# CH340-Sch.net
KiCad netlist of a schematic drawn in Altium Designer
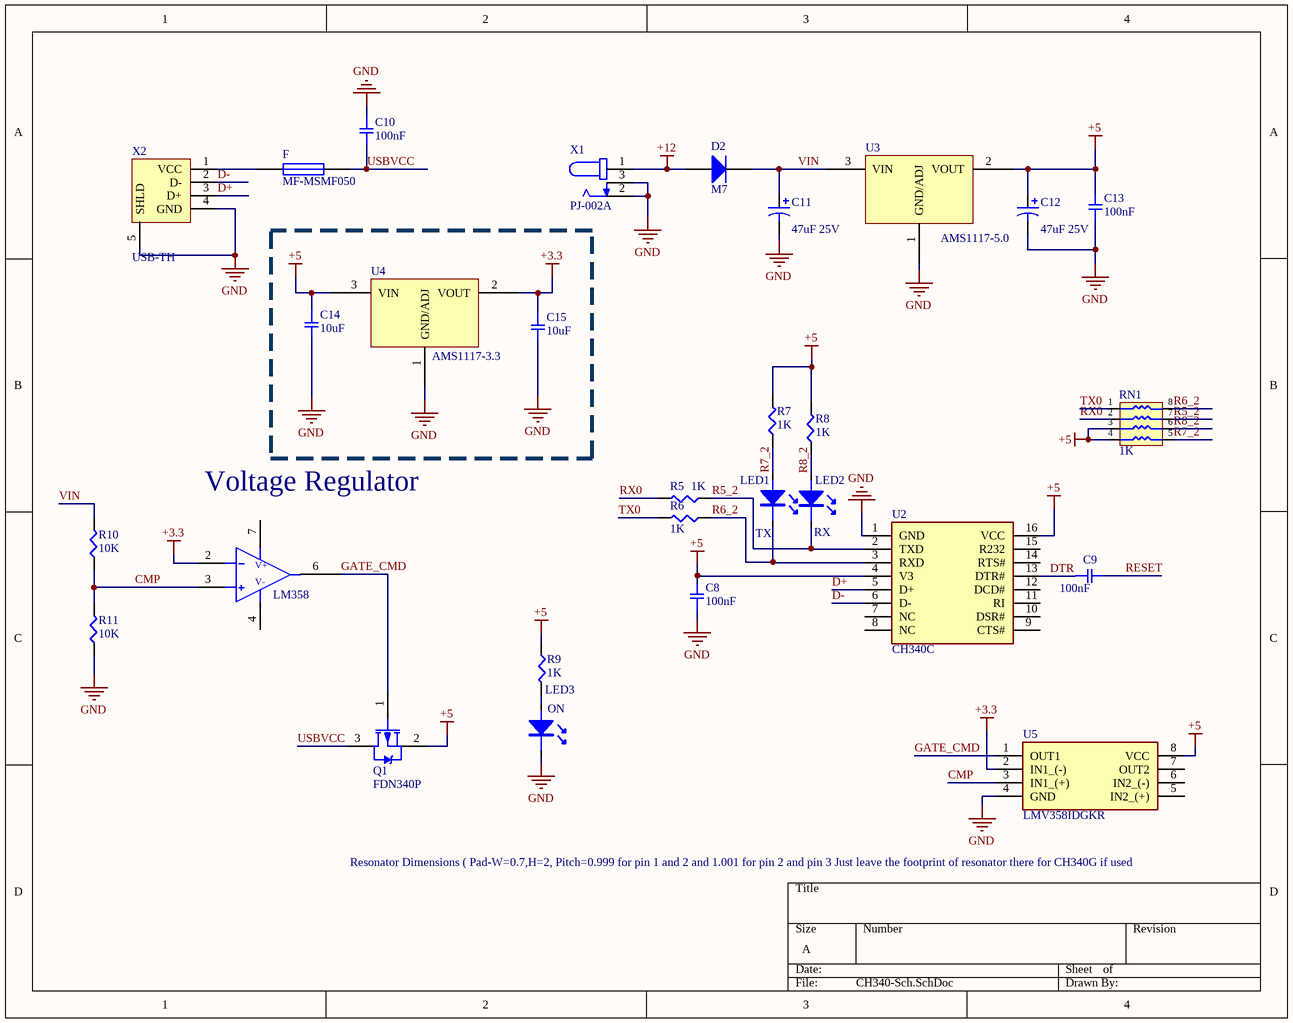
[diagram p0: CH340-Sch.SchDoc]

(export (version "E")
  (design (tool "Eeschema 10.0.6"))
  (components
    (comp (ref "C8")
      (value "100nF")
      (footprint "SMD-0805C")
      (description "CAP CER 10000PF 250V X7T 0805")
      (fields
        (field (name "DIGI-KEY PART NUMBER") "490-13986-1-ND")
        (field (name "PART NUMBER") "GC321AD72E103KX01D")
      )
      (libsource (lib "capacitor0805") (part "GC321AD72E103KX01D"))
    )
    (comp (ref "C9")
      (value "100nF")
      (footprint "SMD-0805C")
      (description "CAP CER 10000PF 250V X7T 0805")
      (fields
        (field (name "DIGI-KEY PART NUMBER") "490-13986-1-ND")
        (field (name "PART NUMBER") "GC321AD72E103KX01D")
      )
      (libsource (lib "capacitor0805") (part "GC321AD72E103KX01D"))
    )
    (comp (ref "C10")
      (value "100nF")
      (footprint "SMD-0805C")
      (description "CAP CER 10000PF 250V X7T 0805")
      (fields
        (field (name "DIGI-KEY PART NUMBER") "490-13986-1-ND")
        (field (name "PART NUMBER") "GC321AD72E103KX01D")
      )
      (libsource (lib "capacitor0805") (part "GC321AD72E103KX01D"))
    )
    (comp (ref "C11")
      (value "47uF 25V")
      (footprint "Elec-Cap-SMD")
      (description "Polarized Capacitor (Axial)")
      (fields (field (name "Comment") "47uF SMD") (field (name "PUBLISHER") "Altium Limited"))
      (libsource (lib "Miscellaneous Devices") (part "Cap Pol2"))
    )
    (comp (ref "C12")
      (value "47uF 25V")
      (footprint "Elec-Cap-SMD")
      (description "Polarized Capacitor (Axial)")
      (fields (field (name "Comment") "47uF SMD") (field (name "PUBLISHER") "Altium Limited"))
      (libsource (lib "Miscellaneous Devices") (part "Cap Pol2"))
    )
    (comp (ref "C13")
      (value "100nF")
      (footprint "SMD-0805C")
      (description "CAP CER 10000PF 250V X7T 0805")
      (fields
        (field (name "DIGI-KEY PART NUMBER") "490-13986-1-ND")
        (field (name "PART NUMBER") "GC321AD72E103KX01D")
      )
      (libsource (lib "capacitor0805") (part "GC321AD72E103KX01D"))
    )
    (comp (ref "C14")
      (value "10uF")
      (footprint "SMD-0805C")
      (description "CAP CER 10000PF 250V X7T 0805")
      (fields
        (field (name "DIGI-KEY PART NUMBER") "490-13986-1-ND")
        (field (name "PART NUMBER") "GC321AD72E103KX01D")
      )
      (libsource (lib "capacitor0805") (part "GC321AD72E103KX01D"))
    )
    (comp (ref "C15")
      (value "10uF")
      (footprint "SMD-0805C")
      (description "CAP CER 10000PF 250V X7T 0805")
      (fields
        (field (name "DIGI-KEY PART NUMBER") "490-13986-1-ND")
        (field (name "PART NUMBER") "GC321AD72E103KX01D")
      )
      (libsource (lib "capacitor0805") (part "GC321AD72E103KX01D"))
    )
    (comp (ref "D2")
      (value "M7")
      (footprint "D0214AC(SMA-2)")
      (description "Default Diode")
      (fields (field (name "PUBLISHER") "Altium Limited"))
      (libsource (lib "Miscellaneous Devices") (part "Diode"))
    )
    (comp (ref "F")
      (value "MF-MSMF050")
      (footprint "MF-MSMF050-2 (LCSC)")
      (description "Fuse")
      (fields (field (name "PUBLISHER") "Altium Limited"))
      (libsource (lib "Miscellaneous Devices") (part "Fuse 1"))
    )
    (comp (ref "LED1")
      (value "TX")
      (footprint "Blue_LED_0805")
      (description "SMT LED")
      (libsource (lib "SMT-LED") (part "LED 5V"))
    )
    (comp (ref "LED2")
      (value "RX")
      (footprint "Blue_LED_0805")
      (description "SMT LED")
      (libsource (lib "SMT-LED") (part "LED 5V"))
    )
    (comp (ref "LED3")
      (value "ON")
      (footprint "RED_LED_0805")
      (description "SMT LED")
      (libsource (lib "SMT-LED") (part "LED 5V"))
    )
    (comp (ref "Q1")
      (value "FDN340P")
      (footprint "SOT-23-3")
      (description "P-Channel  MOSFET SMD CODE=A1SHB")
      (fields (field (name "PUBLISHER") "Altium Limited"))
      (libsource (lib "FDN340P") (part "FDN340P"))
    )
    (comp (ref "R5")
      (value "1K")
      (description "RES SMD 1.1 OHM 1% 1/3W 0805")
      (fields (field (name "PART NUMBER") "ERJ-6BQF1R1V") (field (name "DIGI-KEY PART NUMBER") "P17500CT-ND"))
      (libsource (lib "Res0805") (part "ERJ-6BQF1R1V"))
    )
    (comp (ref "R6")
      (value "1K")
      (description "RES SMD 1.1 OHM 1% 1/3W 0805")
      (fields (field (name "PART NUMBER") "ERJ-6BQF1R1V") (field (name "DIGI-KEY PART NUMBER") "P17500CT-ND"))
      (libsource (lib "Res0805") (part "ERJ-6BQF1R1V"))
    )
    (comp (ref "R7")
      (value "1K")
      (description "RES SMD 1.1 OHM 1% 1/3W 0805")
      (fields (field (name "PART NUMBER") "ERJ-6BQF1R1V") (field (name "DIGI-KEY PART NUMBER") "P17500CT-ND"))
      (libsource (lib "Res0805") (part "ERJ-6BQF1R1V"))
    )
    (comp (ref "R8")
      (value "1K")
      (description "RES SMD 1.1 OHM 1% 1/3W 0805")
      (fields (field (name "PART NUMBER") "ERJ-6BQF1R1V") (field (name "DIGI-KEY PART NUMBER") "P17500CT-ND"))
      (libsource (lib "Res0805") (part "ERJ-6BQF1R1V"))
    )
    (comp (ref "R9")
      (value "1K")
      (footprint "SMD-0805-RES")
      (description "RES SMD 1.1 OHM 1% 1/3W 0805")
      (fields (field (name "PART NUMBER") "ERJ-6BQF1R1V") (field (name "DIGI-KEY PART NUMBER") "P17500CT-ND"))
      (libsource (lib "Res0805") (part "ERJ-6BQF1R1V"))
    )
    (comp (ref "R10")
      (value "10K")
      (footprint "SMD-0805-RES")
      (description "RES SMD 1.1 OHM 1% 1/3W 0805")
      (fields (field (name "PART NUMBER") "ERJ-6BQF1R1V") (field (name "DIGI-KEY PART NUMBER") "P17500CT-ND"))
      (libsource (lib "Res0805") (part "ERJ-6BQF1R1V"))
    )
    (comp (ref "R11")
      (value "10K")
      (footprint "SMD-0805-RES")
      (description "RES SMD 1.1 OHM 1% 1/3W 0805")
      (fields (field (name "PART NUMBER") "ERJ-6BQF1R1V") (field (name "DIGI-KEY PART NUMBER") "P17500CT-ND"))
      (libsource (lib "Res0805") (part "ERJ-6BQF1R1V"))
    )
    (comp (ref "RN1")
      (value "1K")
      (footprint "RA0603-8")
      (fields (field (name "MF") "Yageo") (field (name "MP") "YC164-JR-07330RL"))
      (libsource (lib "ResNetwork(SMD)") (part "RES_NETWORK"))
    )
    (comp (ref "U2")
      (value "CH340C")
      (footprint "SOIC-16 150MIL(LCSC)")
      (description "Integrated Circuit")
      (fields
        (field (name "MANUFACTURER_PART_NUMBER") "DS3231SN#")
        (field (name "MOUSER PART NUMBER") "700-DS3231SN#")
      )
      (libsource (lib "CH340") (part "CH340C"))
    )
    (comp (ref "U3")
      (value "AMS1117-5.0")
      (footprint "SOT-223")
      (description "AMS1117-3.3, Voltage Regulator")
      (libsource (lib "AMS1117") (part "AMS1117"))
    )
    (comp (ref "U4")
      (value "AMS1117-3.3")
      (footprint "SOT-223")
      (description "AMS1117-3.3, Voltage Regulator")
      (libsource (lib "AMS1117") (part "AMS1117"))
    )
    (comp (ref "U5")
      (value "LMV358IDGKR")
      (footprint "VSSOP-8")
      (description "Integrated Circuit")
      (fields
        (field (name "MANUFACTURER_PART_NUMBER") "LM358N")
        (field (name "MOUSER PART NUMBER") "512-LM358N")
      )
      (libsource (lib "LM358") (part "LM358N"))
    )
    (comp (ref "U6")
      (value "LM358")
      (description "4.5MHz BiMOS Op-Amp with Mosfet Input")
      (fields (field (name "PUBLISHER") "Altium Limited"))
      (libsource (lib "Miscellaneous Devices") (part "CA3140"))
    )
    (comp (ref "X1")
      (value "PJ-002A")
      (footprint "PJ-002A")
      (description "2,0 x 6,5 mm, 2,5 A, Yatay, A莽谋k Delik, Dc G眉莽 Jak谋 Konnekt枚r眉")
      (fields (field (name "MF") "CUI Devices"))
      (libsource (lib "Barrel Female Conn") (part "PJ-002A"))
    )
    (comp (ref "X2")
      (value "USB-TH")
      (footprint "USB-TypeB Female (LCSC)")
      (description "USB-Type B Female")
      (libsource (lib "USB-Multi") (part "USB-Type B"))
    )
  )
  (nets
    (net (code "1") (name "+3.3") (class "Default")
      (node (ref "C15") (pin "1") (pinfunction "1_1") (pintype "passive"))
      (node (ref "U4") (pin "2") (pinfunction "VOUT_2") (pintype "passive"))
      (node (ref "U5") (pin "2") (pinfunction "IN1_(-)_2") (pintype "passive"))
      (node (ref "U6") (pin "2") (pinfunction "INV_2") (pintype "passive"))
    )
    (net (code "2") (name "+5") (class "Default")
      (node (ref "C12") (pin "1") (pinfunction "1_1") (pintype "passive"))
      (node (ref "C13") (pin "2") (pinfunction "2_2") (pintype "passive"))
      (node (ref "C14") (pin "1") (pinfunction "1_1") (pintype "passive"))
      (node (ref "C8") (pin "2") (pinfunction "2_2") (pintype "passive"))
      (node (ref "Q1") (pin "2") (pinfunction "S_2") (pintype "passive"))
      (node (ref "R7") (pin "2") (pinfunction "2_2") (pintype "passive"))
      (node (ref "R8") (pin "2") (pinfunction "2_2") (pintype "passive"))
      (node (ref "R9") (pin "1") (pinfunction "1_1") (pintype "passive"))
      (node (ref "RN1") (pin "3") (pinfunction "3_3") (pintype "passive"))
      (node (ref "RN1") (pin "4") (pinfunction "4_4") (pintype "passive"))
      (node (ref "U2") (pin "16") (pinfunction "VCC_16") (pintype "passive"))
      (node (ref "U2") (pin "4") (pinfunction "V3_4") (pintype "passive"))
      (node (ref "U3") (pin "2") (pinfunction "VOUT_2") (pintype "passive"))
      (node (ref "U4") (pin "3") (pinfunction "VIN_3") (pintype "passive"))
      (node (ref "U5") (pin "8") (pinfunction "VCC_8") (pintype "passive"))
    )
    (net (code "3") (name "+12") (class "Default")
      (node (ref "D2") (pin "1") (pinfunction "A_1") (pintype "passive"))
      (node (ref "X1") (pin "1") (pinfunction "1_1") (pintype "passive"))
    )
    (net (code "4") (name "/CMP") (class "Default")
      (node (ref "R10") (pin "1") (pinfunction "1_1") (pintype "passive"))
      (node (ref "R11") (pin "2") (pinfunction "2_2") (pintype "passive"))
      (node (ref "U5") (pin "3") (pinfunction "IN1_(+)_3") (pintype "passive"))
      (node (ref "U6") (pin "3") (pinfunction "NON-INV_3") (pintype "passive"))
    )
    (net (code "5") (name "/D+") (class "Default")
      (node (ref "U2") (pin "5") (pinfunction "D+_5") (pintype "passive"))
      (node (ref "X2") (pin "3") (pinfunction "D+_3") (pintype "passive"))
    )
    (net (code "6") (name "/D-") (class "Default")
      (node (ref "U2") (pin "6") (pinfunction "D-_6") (pintype "passive"))
      (node (ref "X2") (pin "2") (pinfunction "D-_2") (pintype "passive"))
    )
    (net (code "7") (name "/DTR") (class "Default")
      (node (ref "C9") (pin "1") (pinfunction "1_1") (pintype "passive"))
      (node (ref "U2") (pin "13") (pinfunction "DTR#_13") (pintype "power_in"))
    )
    (net (code "8") (name "/GATE_CMD") (class "Default")
      (node (ref "Q1") (pin "1") (pinfunction "G_1") (pintype "passive"))
      (node (ref "U5") (pin "1") (pinfunction "OUT1_1") (pintype "passive"))
      (node (ref "U6") (pin "6") (pinfunction "O/P_6") (pintype "passive"))
    )
    (net (code "9") (name "/R5_2") (class "Default")
      (node (ref "LED2") (pin "2") (pinfunction "K_2") (pintype "passive"))
      (node (ref "R5") (pin "1") (pinfunction "1_1") (pintype "passive"))
      (node (ref "RN1") (pin "7") (pinfunction "7_7") (pintype "passive"))
      (node (ref "U2") (pin "2") (pinfunction "TXD_2") (pintype "power_in"))
    )
    (net (code "10") (name "/R6_2") (class "Default")
      (node (ref "LED1") (pin "2") (pinfunction "K_2") (pintype "passive"))
      (node (ref "R6") (pin "1") (pinfunction "1_1") (pintype "passive"))
      (node (ref "RN1") (pin "8") (pinfunction "8_8") (pintype "passive"))
      (node (ref "U2") (pin "3") (pinfunction "RXD_3") (pintype "passive"))
    )
    (net (code "11") (name "/R7_2") (class "Default")
      (node (ref "LED1") (pin "1") (pinfunction "A_1") (pintype "passive"))
      (node (ref "R7") (pin "1") (pinfunction "1_1") (pintype "passive"))
      (node (ref "RN1") (pin "5") (pinfunction "5_5") (pintype "passive"))
    )
    (net (code "12") (name "/R8_2") (class "Default")
      (node (ref "LED2") (pin "1") (pinfunction "A_1") (pintype "passive"))
      (node (ref "R8") (pin "1") (pinfunction "1_1") (pintype "passive"))
      (node (ref "RN1") (pin "6") (pinfunction "6_6") (pintype "passive"))
    )
    (net (code "13") (name "/RESET") (class "Default")
      (node (ref "C9") (pin "2") (pinfunction "2_2") (pintype "passive"))
    )
    (net (code "14") (name "/RX0") (class "Default")
      (node (ref "R5") (pin "2") (pinfunction "2_2") (pintype "passive"))
      (node (ref "RN1") (pin "2") (pinfunction "2_2") (pintype "passive"))
    )
    (net (code "15") (name "/TX0") (class "Default")
      (node (ref "R6") (pin "2") (pinfunction "2_2") (pintype "passive"))
      (node (ref "RN1") (pin "1") (pinfunction "1_1") (pintype "passive"))
    )
    (net (code "16") (name "/USBVCC") (class "Default")
      (node (ref "C10") (pin "1") (pinfunction "1_1") (pintype "passive"))
      (node (ref "F") (pin "2") (pinfunction "2_2") (pintype "passive"))
      (node (ref "Q1") (pin "3") (pinfunction "D_3") (pintype "passive"))
    )
    (net (code "17") (name "/VIN") (class "Default")
      (node (ref "C11") (pin "1") (pinfunction "1_1") (pintype "passive"))
      (node (ref "D2") (pin "2") (pinfunction "K_2") (pintype "passive"))
      (node (ref "R10") (pin "2") (pinfunction "2_2") (pintype "passive"))
      (node (ref "U3") (pin "3") (pinfunction "VIN_3") (pintype "passive"))
    )
    (net (code "18") (name "GND") (class "Default")
      (node (ref "C10") (pin "2") (pinfunction "2_2") (pintype "passive"))
      (node (ref "C11") (pin "2") (pinfunction "2_2") (pintype "passive"))
      (node (ref "C12") (pin "2") (pinfunction "2_2") (pintype "passive"))
      (node (ref "C13") (pin "1") (pinfunction "1_1") (pintype "passive"))
      (node (ref "C14") (pin "2") (pinfunction "2_2") (pintype "passive"))
      (node (ref "C15") (pin "2") (pinfunction "2_2") (pintype "passive"))
      (node (ref "C8") (pin "1") (pinfunction "1_1") (pintype "passive"))
      (node (ref "LED3") (pin "2") (pinfunction "K_2") (pintype "passive"))
      (node (ref "R11") (pin "1") (pinfunction "1_1") (pintype "passive"))
      (node (ref "U2") (pin "1") (pinfunction "GND_1") (pintype "passive"))
      (node (ref "U3") (pin "1") (pinfunction "GND/ADJ_1") (pintype "passive"))
      (node (ref "U4") (pin "1") (pinfunction "GND/ADJ_1") (pintype "passive"))
      (node (ref "U5") (pin "4") (pinfunction "GND_4") (pintype "passive"))
      (node (ref "X1") (pin "2") (pinfunction "2_2") (pintype "passive"))
      (node (ref "X1") (pin "3") (pinfunction "3_3") (pintype "passive"))
      (node (ref "X2") (pin "4") (pinfunction "GND_4") (pintype "passive"))
      (node (ref "X2") (pin "5") (pinfunction "SHLD_5") (pintype "passive"))
    )
    (net (code "19") (name "Net-(LED3-A)") (class "Default")
      (node (ref "LED3") (pin "1") (pinfunction "A_1") (pintype "passive"))
      (node (ref "R9") (pin "2") (pinfunction "2_2") (pintype "passive"))
    )
    (net (code "20") (name "Net-(X2-VCC)") (class "Default")
      (node (ref "F") (pin "1") (pinfunction "1_1") (pintype "passive"))
      (node (ref "X2") (pin "1") (pinfunction "VCC_1") (pintype "passive"))
    )
    (net (code "21") (name "unconnected-(U2-CTS#-Pad9)") (class "Default")
      (node (ref "U2") (pin "9") (pinfunction "CTS#_9") (pintype "passive"))
    )
    (net (code "22") (name "unconnected-(U2-DCD#-Pad12)") (class "Default")
      (node (ref "U2") (pin "12") (pinfunction "DCD#_12") (pintype "passive"))
    )
    (net (code "23") (name "unconnected-(U2-DSR#-Pad10)") (class "Default")
      (node (ref "U2") (pin "10") (pinfunction "DSR#_10") (pintype "passive"))
    )
    (net (code "24") (name "unconnected-(U2-NC-Pad7)") (class "Default")
      (node (ref "U2") (pin "7") (pinfunction "NC_7") (pintype "passive"))
    )
    (net (code "25") (name "unconnected-(U2-NC-Pad8)") (class "Default")
      (node (ref "U2") (pin "8") (pinfunction "NC_8") (pintype "passive"))
    )
    (net (code "26") (name "unconnected-(U2-R232-Pad15)") (class "Default")
      (node (ref "U2") (pin "15") (pinfunction "R232_15") (pintype "passive"))
    )
    (net (code "27") (name "unconnected-(U2-RI-Pad11)") (class "Default")
      (node (ref "U2") (pin "11") (pinfunction "RI_11") (pintype "passive"))
    )
    (net (code "28") (name "unconnected-(U2-RTS#-Pad14)") (class "Default")
      (node (ref "U2") (pin "14") (pinfunction "RTS#_14") (pintype "passive"))
    )
    (net (code "29") (name "unconnected-(U5-IN2_(+)-Pad5)") (class "Default")
      (node (ref "U5") (pin "5") (pinfunction "IN2_(+)_5") (pintype "passive"))
    )
    (net (code "30") (name "unconnected-(U5-IN2_(-)-Pad6)") (class "Default")
      (node (ref "U5") (pin "6") (pinfunction "IN2_(-)_6") (pintype "passive"))
    )
    (net (code "31") (name "unconnected-(U5-OUT2-Pad7)") (class "Default")
      (node (ref "U5") (pin "7") (pinfunction "OUT2_7") (pintype "passive"))
    )
    (net (code "32") (name "unconnected-(U6-GND-Pad4)") (class "Default")
      (node (ref "U6") (pin "4") (pinfunction "GND_4") (pintype "passive"))
    )
    (net (code "33") (name "unconnected-(U6-VCC-Pad7)") (class "Default")
      (node (ref "U6") (pin "7") (pinfunction "VCC_7") (pintype "passive"))
    )
  )
)
